# USB_Connector.net
KiCad netlist of a schematic drawn in Altium Designer
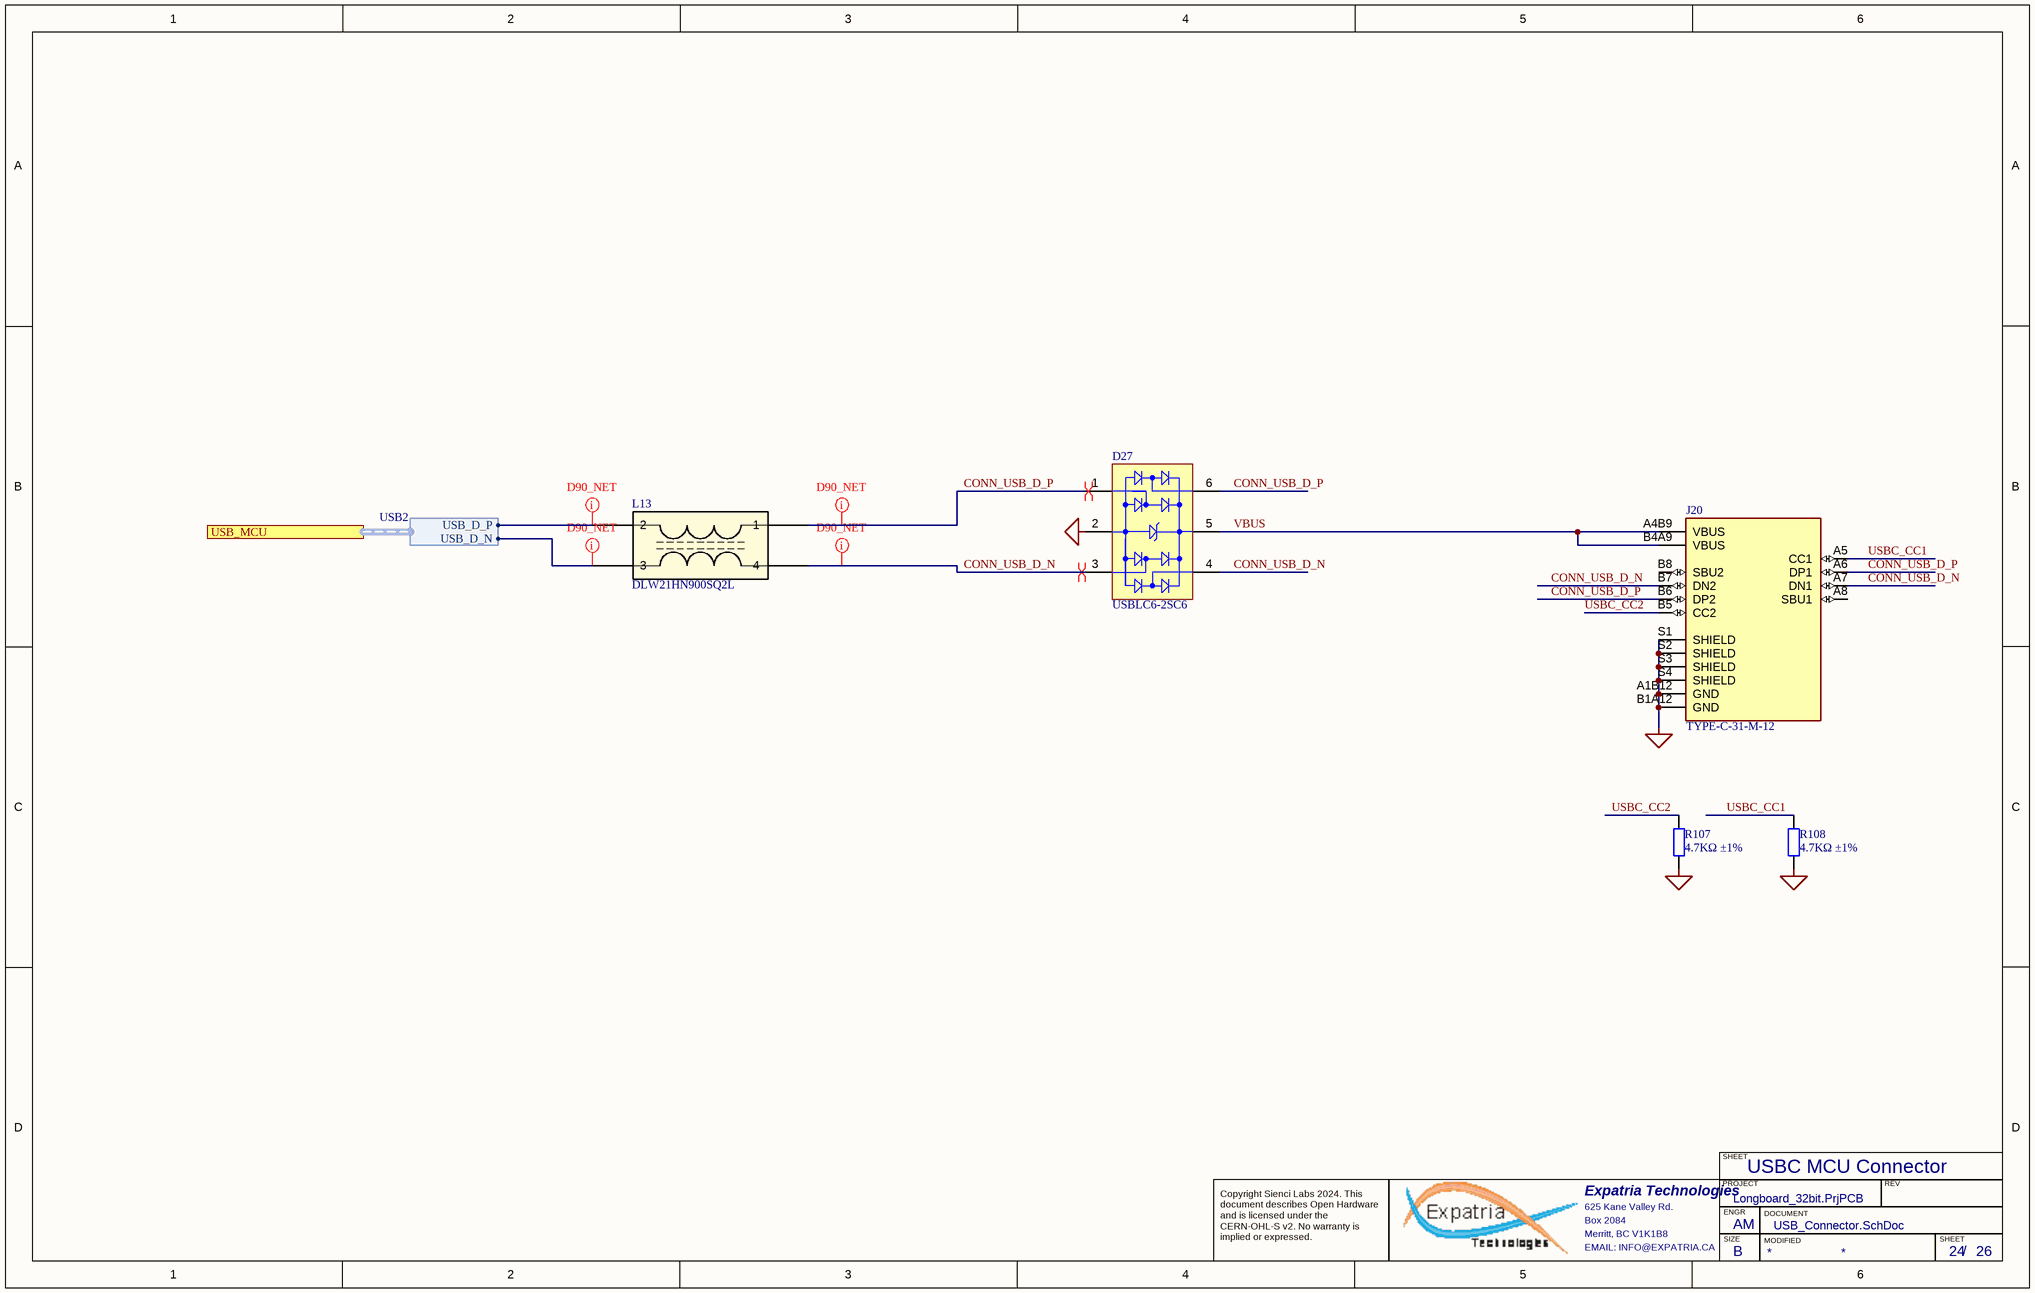
[diagram p0: USB_Connector.SchDoc]

(export (version "E")
  (design (tool "Eeschema 10.0.6"))
  (components
    (comp (ref "D27")
      (value "USBLC6-2SC6")
      (footprint "SOT95P280X145-6N")
      (description "Very low capacitance ESD protection, 3.5 pF, -40 to 125 degC, 6-Pin SOT23, RoHS, Tape and Reel")
      (fields (field (name "MANUFACTURER") "TECH PUBLIC"))
      (libsource (lib "Sienci_Labs") (part "USBLC6-2SC6"))
    )
    (comp (ref "J20")
      (value "TYPE-C-31-M-12")
      (footprint "HRO_TYPE-C-31-M-12")
      (description "USB Connectors 24 Receptacle 1 8.94*7.3mm RoHS")
      (fields (field (name "MANUFACTURER") "HRO Electronics Co., Ltd."))
      (libsource (lib "Universal_CNC_Breakout") (part "TYPE-C-31-M-12"))
    )
    (comp (ref "L13")
      (value "DLW21HN900SQ2L")
      (footprint "DLW21HN121HQ2B")
      (description "90Ω@100MHz -40℃~+85℃ 350mΩ 50V 2 330mA 125V SMD-4P Common Mode Filters ROHS")
      (fields (field (name "MANUFACTURER") "Murata Electronics"))
      (libsource (lib "Sienci_Labs") (part "DLW21HN900SQ2L"))
    )
    (comp (ref "R107")
      (value "4.7KΩ ±1%")
      (footprint "0603_R")
      (description "Chip resistor")
      (fields
        (field (name "MANUFACTURER") "Uniroyal Elec")
        (field (name "MANUFACTURER PART NUMBER") "0603WAF4701T5E")
      )
      (libsource (lib "RES") (part "0603 4.7K (4701) 1%"))
    )
    (comp (ref "R108")
      (value "4.7KΩ ±1%")
      (footprint "0603_R")
      (description "Chip resistor")
      (fields
        (field (name "MANUFACTURER") "Uniroyal Elec")
        (field (name "MANUFACTURER PART NUMBER") "0603WAF4701T5E")
      )
      (libsource (lib "RES") (part "0603 4.7K (4701) 1%"))
    )
  )
  (nets
    (net (code "2") (name "/CONN_USB_D_N") (class "Default")
      (node (ref "D27") (pin "3") (pinfunction "I/O_2_3") (pintype "passive"))
      (node (ref "D27") (pin "4") (pinfunction "I/O_3_4") (pintype "passive"))
      (node (ref "J20") (pin "A7") (pinfunction "DN1_A7") (pintype "bidirectional"))
      (node (ref "J20") (pin "B7") (pinfunction "DN2_B7") (pintype "bidirectional"))
      (node (ref "L13") (pin "4") (pinfunction "4_4") (pintype "passive"))
    )
    (net (code "3") (name "/CONN_USB_D_P") (class "Default")
      (node (ref "D27") (pin "1") (pinfunction "I/O_1_1") (pintype "passive"))
      (node (ref "D27") (pin "6") (pinfunction "I/O_4_6") (pintype "passive"))
      (node (ref "J20") (pin "A6") (pinfunction "DP1_A6") (pintype "bidirectional"))
      (node (ref "J20") (pin "B6") (pinfunction "DP2_B6") (pintype "bidirectional"))
      (node (ref "L13") (pin "1") (pinfunction "1_1") (pintype "passive"))
    )
    (net (code "4") (name "/USBC_CC1") (class "Default")
      (node (ref "J20") (pin "A5") (pinfunction "CC1_A5") (pintype "bidirectional"))
      (node (ref "R108") (pin "1") (pinfunction "1_1") (pintype "passive"))
    )
    (net (code "5") (name "/USBC_CC2") (class "Default")
      (node (ref "J20") (pin "B5") (pinfunction "CC2_B5") (pintype "bidirectional"))
      (node (ref "R107") (pin "1") (pinfunction "1_1") (pintype "passive"))
    )
    (net (code "6") (name "/USB_D_N") (class "Default")
      (node (ref "L13") (pin "3") (pinfunction "3_3") (pintype "passive"))
    )
    (net (code "7") (name "/USB_D_P") (class "Default")
      (node (ref "L13") (pin "2") (pinfunction "2_2") (pintype "passive"))
    )
    (net (code "8") (name "/VBUS") (class "Default")
      (node (ref "D27") (pin "5") (pinfunction "VBUS_5") (pintype "passive"))
      (node (ref "J20") (pin "A4B9") (pinfunction "VBUS_A4B9") (pintype "power_in"))
      (node (ref "J20") (pin "B4A9") (pinfunction "VBUS_B4A9") (pintype "power_in"))
    )
    (net (code "10") (name "MCU_GND") (class "Default")
      (node (ref "D27") (pin "2") (pinfunction "GND_2") (pintype "passive"))
      (node (ref "J20") (pin "A1B12") (pinfunction "GND_A1B12") (pintype "power_in"))
      (node (ref "J20") (pin "B1A12") (pinfunction "GND_B1A12") (pintype "power_in"))
      (node (ref "J20") (pin "S1") (pinfunction "SHIELD_S1") (pintype "passive"))
      (node (ref "J20") (pin "S2") (pinfunction "SHIELD_S2") (pintype "passive"))
      (node (ref "J20") (pin "S3") (pinfunction "SHIELD_S3") (pintype "passive"))
      (node (ref "J20") (pin "S4") (pinfunction "SHIELD_S4") (pintype "passive"))
      (node (ref "R107") (pin "2") (pinfunction "2_2") (pintype "passive"))
      (node (ref "R108") (pin "2") (pinfunction "2_2") (pintype "passive"))
    )
    (net (code "11") (name "unconnected-(J20-SBU1-PadA8)") (class "Default")
      (node (ref "J20") (pin "A8") (pinfunction "SBU1_A8") (pintype "bidirectional"))
    )
    (net (code "12") (name "unconnected-(J20-SBU2-PadB8)") (class "Default")
      (node (ref "J20") (pin "B8") (pinfunction "SBU2_B8") (pintype "bidirectional"))
    )
  )
)
